# tm4cShield_v2_0.net
KiCad netlist of a schematic drawn in EAGLE
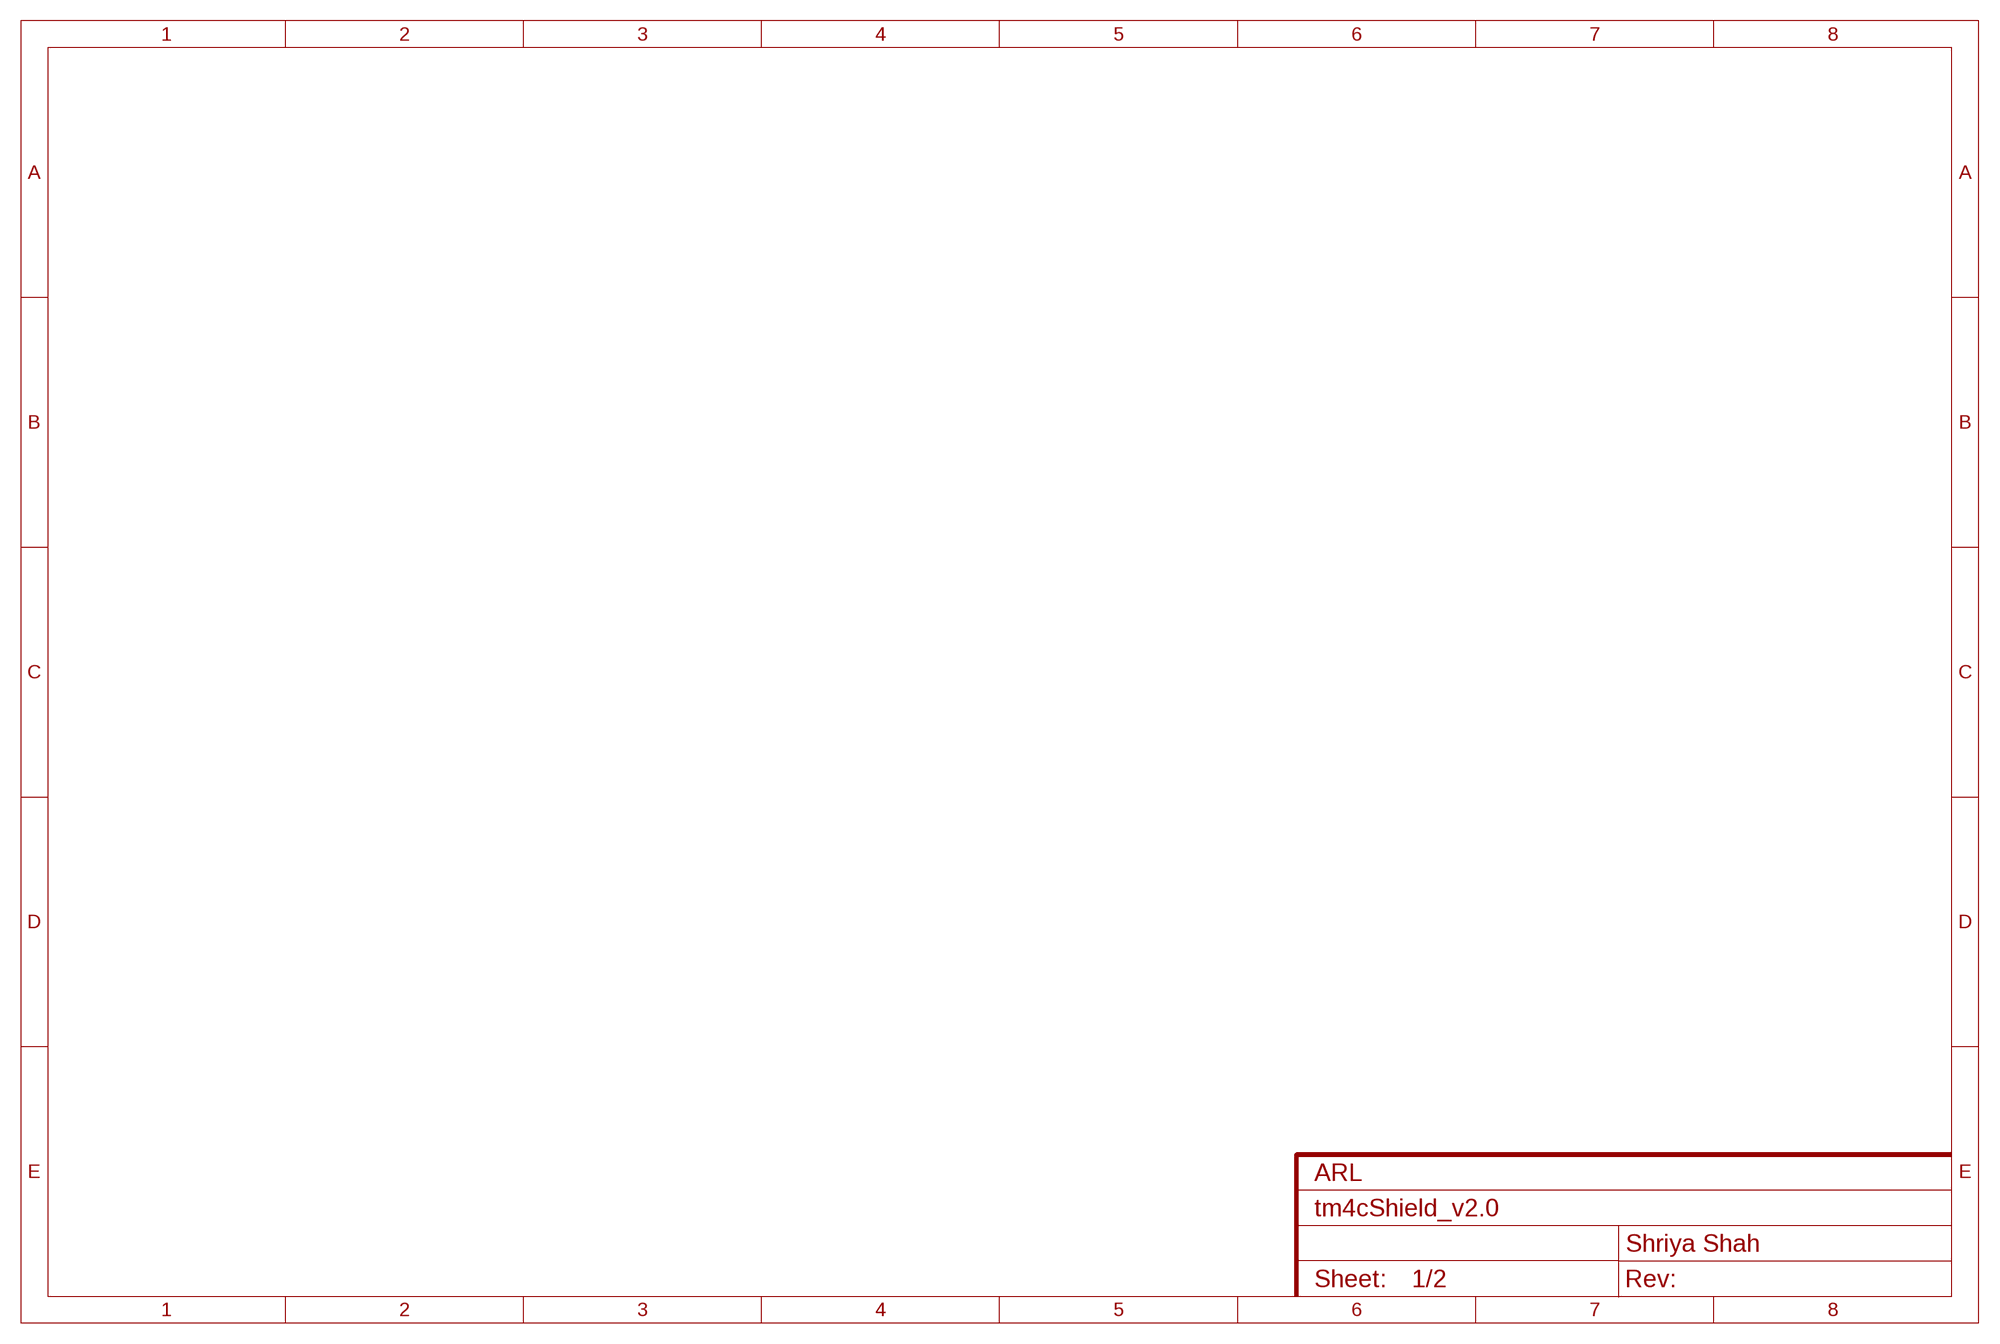
[diagram p0: schematic, sheet 1]
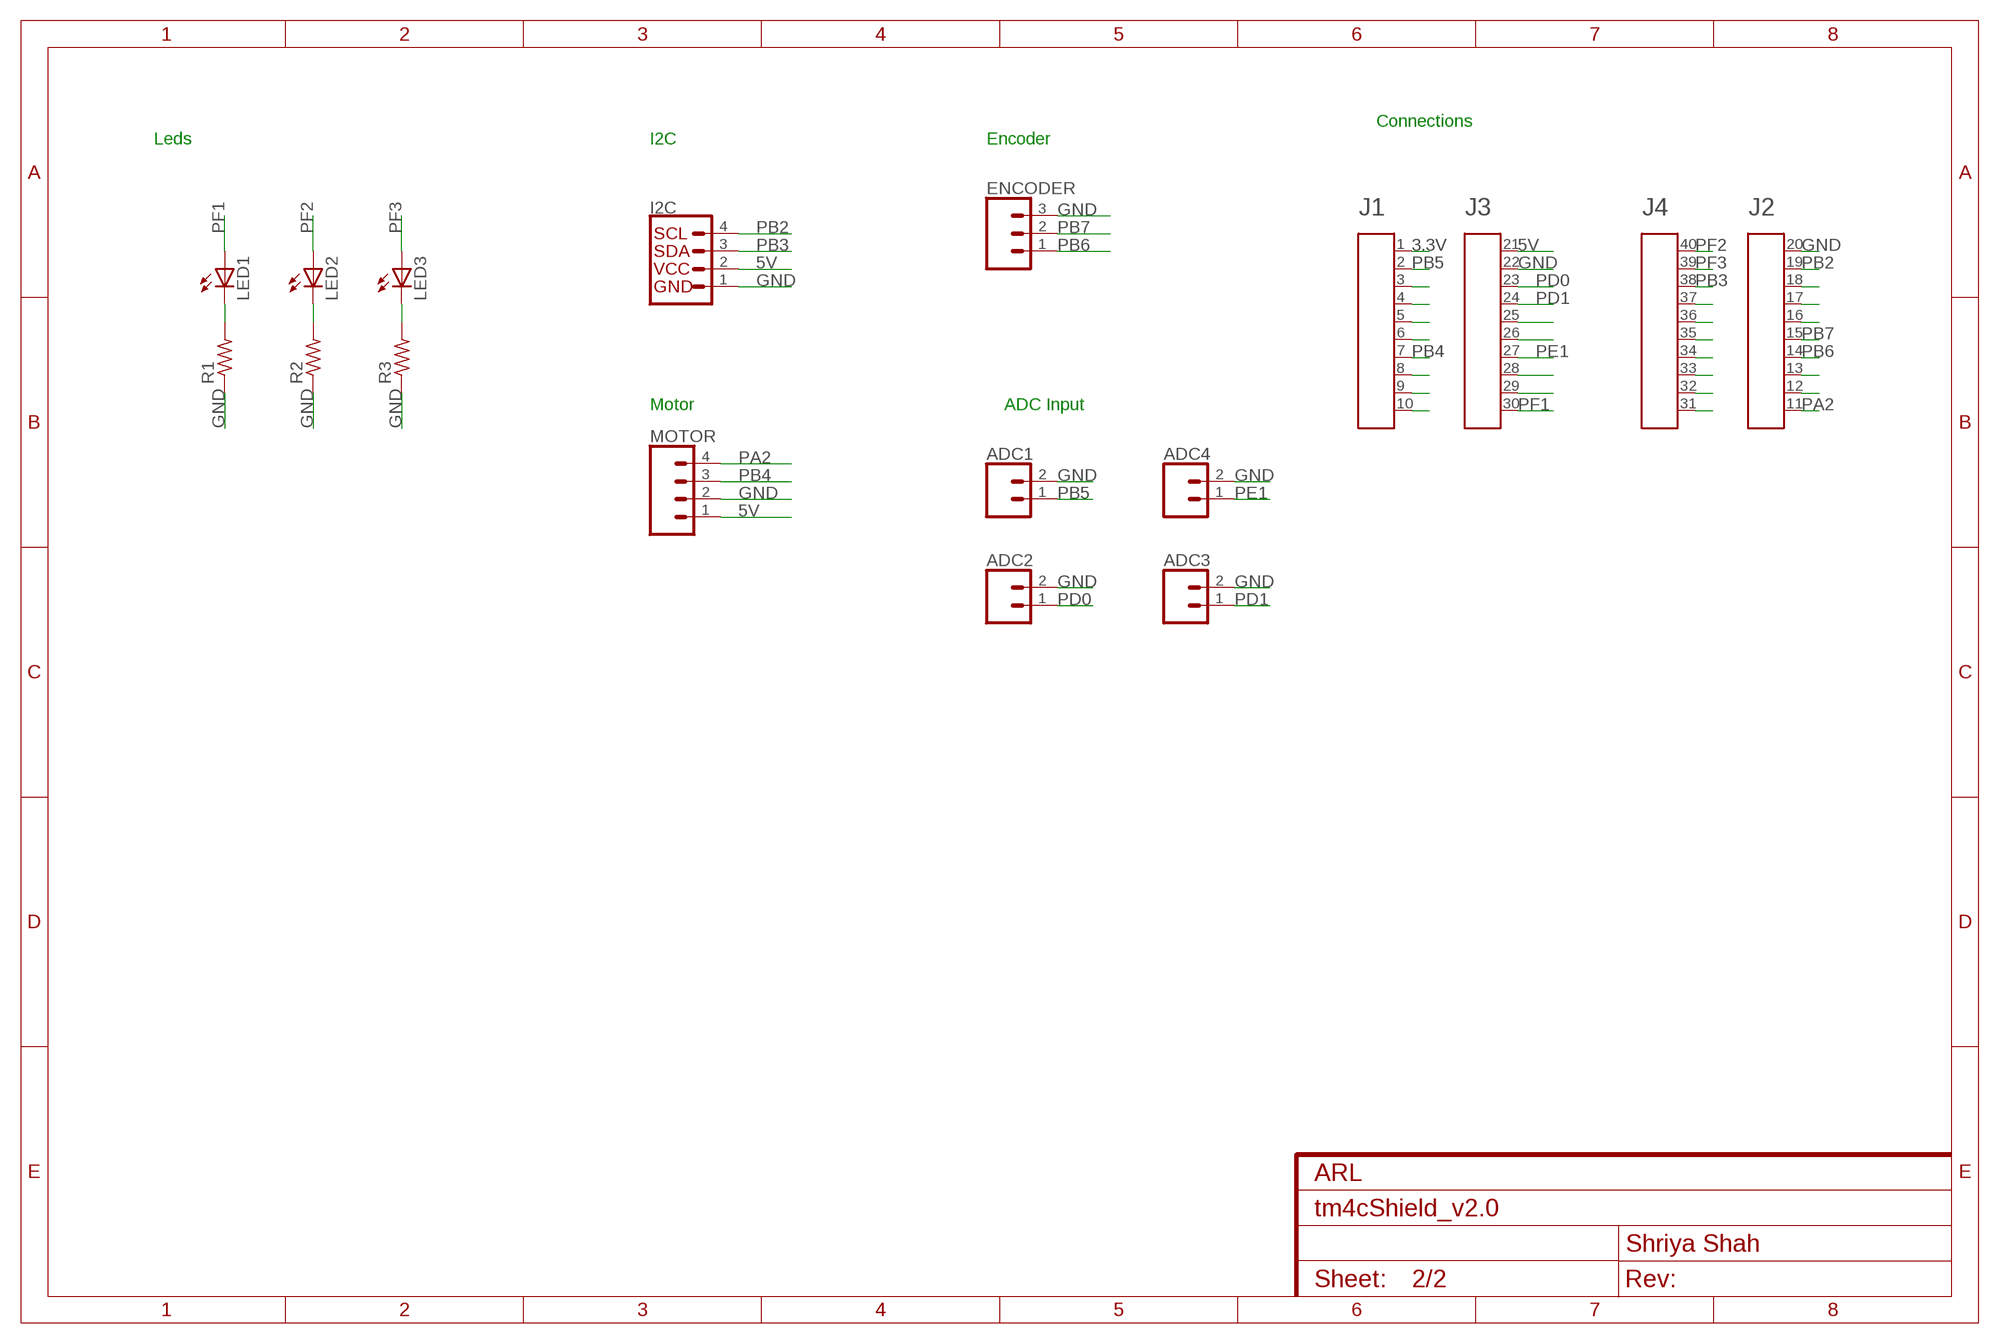
[diagram p1: schematic, sheet 2]

(export (version "E")
  (design (tool "Eeschema 10.0.6"))
  (components
    (comp (ref "A1")
      (value "HEADER4X10-BOOSTERPACK")
      (footprint "eagle-import:4X10-BOOSTERPACK")
      (libsource (lib "eagle-import") (part "HEADER4X10-BOOSTERPACK"))
    )
    (comp (ref "ADC1")
      (value "CONN_02")
      (footprint "eagle-import:1X02")
      (libsource (lib "eagle-import") (part "CONN_02"))
    )
    (comp (ref "ADC2")
      (value "CONN_02")
      (footprint "eagle-import:1X02")
      (libsource (lib "eagle-import") (part "CONN_02"))
    )
    (comp (ref "ADC3")
      (value "CONN_02")
      (footprint "eagle-import:1X02")
      (libsource (lib "eagle-import") (part "CONN_02"))
    )
    (comp (ref "ADC4")
      (value "CONN_02")
      (footprint "eagle-import:1X02")
      (libsource (lib "eagle-import") (part "CONN_02"))
    )
    (comp (ref "ENCODER")
      (value "CONN_03JST-PTH-VERT")
      (footprint "eagle-import:JST-3-PTH-VERT")
      (libsource (lib "eagle-import") (part "CONN_03JST-PTH-VERT"))
    )
    (comp (ref "I2C")
      (value "I2C_STANDARD")
      (footprint "eagle-import:1X04")
      (libsource (lib "eagle-import") (part "I2C_STANDARD"))
    )
    (comp (ref "LED1")
      (value "LED0603")
      (footprint "eagle-import:LED-0603")
      (libsource (lib "eagle-import") (part "LED0603"))
    )
    (comp (ref "LED2")
      (value "LED0603")
      (footprint "eagle-import:LED-0603")
      (libsource (lib "eagle-import") (part "LED0603"))
    )
    (comp (ref "LED3")
      (value "LED0603")
      (footprint "eagle-import:LED-0603")
      (libsource (lib "eagle-import") (part "LED0603"))
    )
    (comp (ref "MOTOR")
      (value "CONN_04JST-PTH-VERT")
      (footprint "eagle-import:JST-4-PTH-VERT")
      (libsource (lib "eagle-import") (part "CONN_04JST-PTH-VERT"))
    )
    (comp (ref "R1")
      (value "RESISTOR_0603")
      (footprint "eagle-import:RESC0603")
      (libsource (lib "eagle-import") (part "RESISTOR_0603"))
    )
    (comp (ref "R2")
      (value "RESISTOR_0603")
      (footprint "eagle-import:RESC0603")
      (libsource (lib "eagle-import") (part "RESISTOR_0603"))
    )
    (comp (ref "R3")
      (value "RESISTOR_0603")
      (footprint "eagle-import:RESC0603")
      (libsource (lib "eagle-import") (part "RESISTOR_0603"))
    )
  )
  (nets
    (net (code "1") (name "3.3V") (class "Default")
      (node (ref "A1") (pin "1") (pinfunction "P$1_1") (pintype "bidirectional"))
    )
    (net (code "2") (name "5V") (class "Default")
      (node (ref "A1") (pin "21") (pinfunction "P$21_21") (pintype "bidirectional"))
      (node (ref "I2C") (pin "2") (pinfunction "2_2") (pintype "power_in"))
      (node (ref "MOTOR") (pin "1") (pinfunction "1_1") (pintype "passive"))
    )
    (net (code "3") (name "GND") (class "Default")
      (node (ref "A1") (pin "20") (pinfunction "P$20_20") (pintype "bidirectional"))
      (node (ref "A1") (pin "22") (pinfunction "P$22_22") (pintype "bidirectional"))
      (node (ref "ADC1") (pin "2") (pinfunction "2_2") (pintype "passive"))
      (node (ref "ADC2") (pin "2") (pinfunction "2_2") (pintype "passive"))
      (node (ref "ADC3") (pin "2") (pinfunction "2_2") (pintype "passive"))
      (node (ref "ADC4") (pin "2") (pinfunction "2_2") (pintype "passive"))
      (node (ref "ENCODER") (pin "3") (pinfunction "3_3") (pintype "passive"))
      (node (ref "I2C") (pin "1") (pinfunction "1_1") (pintype "power_in"))
      (node (ref "MOTOR") (pin "2") (pinfunction "2_2") (pintype "passive"))
      (node (ref "R1") (pin "1") (pinfunction "1_1") (pintype "passive"))
      (node (ref "R2") (pin "1") (pinfunction "1_1") (pintype "passive"))
      (node (ref "R3") (pin "1") (pinfunction "1_1") (pintype "passive"))
    )
    (net (code "4") (name "Net-(LED1-PadC)") (class "Default")
      (node (ref "LED1") (pin "C") (pinfunction "C_C") (pintype "passive"))
      (node (ref "R1") (pin "2") (pinfunction "2_2") (pintype "passive"))
    )
    (net (code "5") (name "Net-(LED2-PadC)") (class "Default")
      (node (ref "LED2") (pin "C") (pinfunction "C_C") (pintype "passive"))
      (node (ref "R2") (pin "2") (pinfunction "2_2") (pintype "passive"))
    )
    (net (code "6") (name "Net-(LED3-PadC)") (class "Default")
      (node (ref "LED3") (pin "C") (pinfunction "C_C") (pintype "passive"))
      (node (ref "R3") (pin "2") (pinfunction "2_2") (pintype "passive"))
    )
    (net (code "7") (name "PA2") (class "Default")
      (node (ref "A1") (pin "11") (pinfunction "P$11_11") (pintype "bidirectional"))
      (node (ref "MOTOR") (pin "4") (pinfunction "4_4") (pintype "passive"))
    )
    (net (code "8") (name "PB2") (class "Default")
      (node (ref "A1") (pin "19") (pinfunction "P$19_19") (pintype "bidirectional"))
      (node (ref "I2C") (pin "4") (pinfunction "4_4") (pintype "passive"))
    )
    (net (code "9") (name "PB3") (class "Default")
      (node (ref "A1") (pin "38") (pinfunction "P$38_38") (pintype "bidirectional"))
      (node (ref "I2C") (pin "3") (pinfunction "3_3") (pintype "passive"))
    )
    (net (code "10") (name "PB4") (class "Default")
      (node (ref "A1") (pin "7") (pinfunction "P$7_7") (pintype "bidirectional"))
      (node (ref "MOTOR") (pin "3") (pinfunction "3_3") (pintype "passive"))
    )
    (net (code "11") (name "PB5") (class "Default")
      (node (ref "A1") (pin "2") (pinfunction "P$2_2") (pintype "bidirectional"))
      (node (ref "ADC1") (pin "1") (pinfunction "1_1") (pintype "passive"))
    )
    (net (code "12") (name "PB6") (class "Default")
      (node (ref "A1") (pin "14") (pinfunction "P$14_14") (pintype "bidirectional"))
      (node (ref "ENCODER") (pin "1") (pinfunction "1_1") (pintype "passive"))
    )
    (net (code "13") (name "PB7") (class "Default")
      (node (ref "A1") (pin "15") (pinfunction "P$15_15") (pintype "bidirectional"))
      (node (ref "ENCODER") (pin "2") (pinfunction "2_2") (pintype "passive"))
    )
    (net (code "14") (name "PD0") (class "Default")
      (node (ref "A1") (pin "23") (pinfunction "P$23_23") (pintype "bidirectional"))
      (node (ref "ADC2") (pin "1") (pinfunction "1_1") (pintype "passive"))
    )
    (net (code "15") (name "PD1") (class "Default")
      (node (ref "A1") (pin "24") (pinfunction "P$24_24") (pintype "bidirectional"))
      (node (ref "ADC3") (pin "1") (pinfunction "1_1") (pintype "passive"))
    )
    (net (code "16") (name "PE1") (class "Default")
      (node (ref "A1") (pin "27") (pinfunction "P$27_27") (pintype "bidirectional"))
      (node (ref "ADC4") (pin "1") (pinfunction "1_1") (pintype "passive"))
    )
    (net (code "17") (name "PF1") (class "Default")
      (node (ref "A1") (pin "30") (pinfunction "P$30_30") (pintype "bidirectional"))
      (node (ref "LED1") (pin "A") (pinfunction "A_A") (pintype "passive"))
    )
    (net (code "18") (name "PF2") (class "Default")
      (node (ref "A1") (pin "40") (pinfunction "P$40_40") (pintype "bidirectional"))
      (node (ref "LED2") (pin "A") (pinfunction "A_A") (pintype "passive"))
    )
    (net (code "19") (name "PF3") (class "Default")
      (node (ref "A1") (pin "39") (pinfunction "P$39_39") (pintype "bidirectional"))
      (node (ref "LED3") (pin "A") (pinfunction "A_A") (pintype "passive"))
    )
    (net (code "20") (name "unconnected-(A1-P$3-Pad3)") (class "Default")
      (node (ref "A1") (pin "3") (pinfunction "P$3_3") (pintype "bidirectional"))
    )
    (net (code "21") (name "unconnected-(A1-P$4-Pad4)") (class "Default")
      (node (ref "A1") (pin "4") (pinfunction "P$4_4") (pintype "bidirectional"))
    )
    (net (code "22") (name "unconnected-(A1-P$5-Pad5)") (class "Default")
      (node (ref "A1") (pin "5") (pinfunction "P$5_5") (pintype "bidirectional"))
    )
    (net (code "23") (name "unconnected-(A1-P$6-Pad6)") (class "Default")
      (node (ref "A1") (pin "6") (pinfunction "P$6_6") (pintype "bidirectional"))
    )
    (net (code "24") (name "unconnected-(A1-P$8-Pad8)") (class "Default")
      (node (ref "A1") (pin "8") (pinfunction "P$8_8") (pintype "bidirectional"))
    )
    (net (code "25") (name "unconnected-(A1-P$9-Pad9)") (class "Default")
      (node (ref "A1") (pin "9") (pinfunction "P$9_9") (pintype "bidirectional"))
    )
    (net (code "26") (name "unconnected-(A1-P$10-Pad10)") (class "Default")
      (node (ref "A1") (pin "10") (pinfunction "P$10_10") (pintype "bidirectional"))
    )
    (net (code "27") (name "unconnected-(A1-P$12-Pad12)") (class "Default")
      (node (ref "A1") (pin "12") (pinfunction "P$12_12") (pintype "bidirectional"))
    )
    (net (code "28") (name "unconnected-(A1-P$13-Pad13)") (class "Default")
      (node (ref "A1") (pin "13") (pinfunction "P$13_13") (pintype "bidirectional"))
    )
    (net (code "29") (name "unconnected-(A1-P$16-Pad16)") (class "Default")
      (node (ref "A1") (pin "16") (pinfunction "P$16_16") (pintype "bidirectional"))
    )
    (net (code "30") (name "unconnected-(A1-P$17-Pad17)") (class "Default")
      (node (ref "A1") (pin "17") (pinfunction "P$17_17") (pintype "bidirectional"))
    )
    (net (code "31") (name "unconnected-(A1-P$18-Pad18)") (class "Default")
      (node (ref "A1") (pin "18") (pinfunction "P$18_18") (pintype "bidirectional"))
    )
    (net (code "32") (name "unconnected-(A1-P$25-Pad25)") (class "Default")
      (node (ref "A1") (pin "25") (pinfunction "P$25_25") (pintype "bidirectional"))
    )
    (net (code "33") (name "unconnected-(A1-P$26-Pad26)") (class "Default")
      (node (ref "A1") (pin "26") (pinfunction "P$26_26") (pintype "bidirectional"))
    )
    (net (code "34") (name "unconnected-(A1-P$28-Pad28)") (class "Default")
      (node (ref "A1") (pin "28") (pinfunction "P$28_28") (pintype "bidirectional"))
    )
    (net (code "35") (name "unconnected-(A1-P$29-Pad29)") (class "Default")
      (node (ref "A1") (pin "29") (pinfunction "P$29_29") (pintype "bidirectional"))
    )
    (net (code "36") (name "unconnected-(A1-P$31-Pad31)") (class "Default")
      (node (ref "A1") (pin "31") (pinfunction "P$31_31") (pintype "bidirectional"))
    )
    (net (code "37") (name "unconnected-(A1-P$32-Pad32)") (class "Default")
      (node (ref "A1") (pin "32") (pinfunction "P$32_32") (pintype "bidirectional"))
    )
    (net (code "38") (name "unconnected-(A1-P$33-Pad33)") (class "Default")
      (node (ref "A1") (pin "33") (pinfunction "P$33_33") (pintype "bidirectional"))
    )
    (net (code "39") (name "unconnected-(A1-P$34-Pad34)") (class "Default")
      (node (ref "A1") (pin "34") (pinfunction "P$34_34") (pintype "bidirectional"))
    )
    (net (code "40") (name "unconnected-(A1-P$35-Pad35)") (class "Default")
      (node (ref "A1") (pin "35") (pinfunction "P$35_35") (pintype "bidirectional"))
    )
    (net (code "41") (name "unconnected-(A1-P$36-Pad36)") (class "Default")
      (node (ref "A1") (pin "36") (pinfunction "P$36_36") (pintype "bidirectional"))
    )
    (net (code "42") (name "unconnected-(A1-P$37-Pad37)") (class "Default")
      (node (ref "A1") (pin "37") (pinfunction "P$37_37") (pintype "bidirectional"))
    )
  )
)
